# TopBoard.net
KiCad netlist of a schematic drawn in Altium Designer
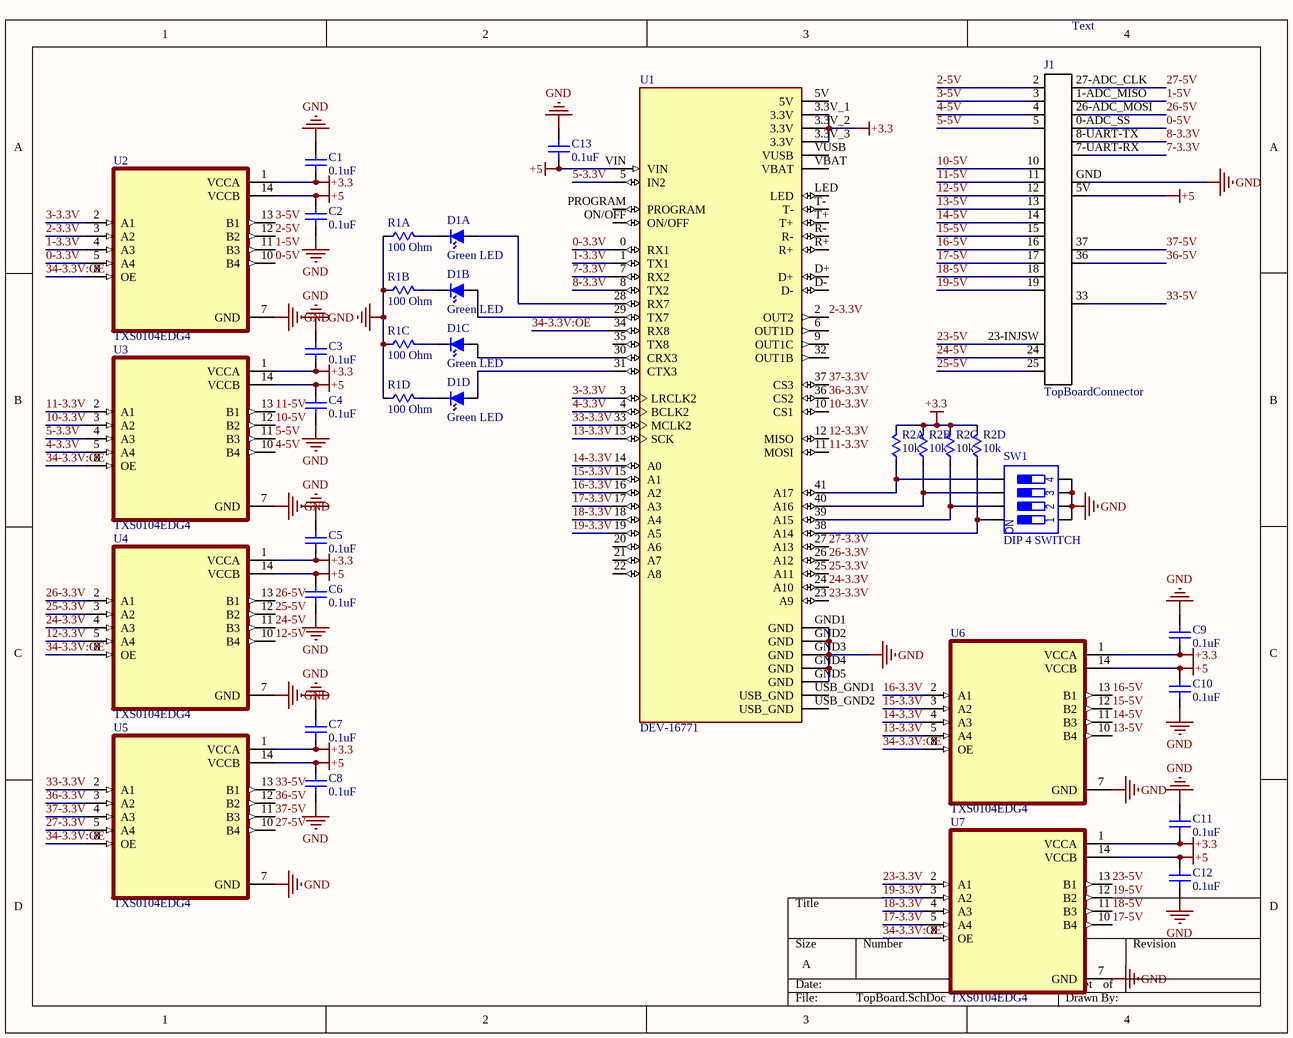
[diagram p0: TopBoard.SchDoc]

(export (version "E")
  (design (tool "Eeschema 10.0.6"))
  (components
    (comp (ref "C1")
      (value "0.1uF")
      (footprint "0805")
      (description "Cap 0805")
      (libsource (lib "Caps") (part "Cap_0805"))
    )
    (comp (ref "C2")
      (value "0.1uF")
      (footprint "0805")
      (description "Cap 0805")
      (libsource (lib "Caps") (part "Cap_0805"))
    )
    (comp (ref "C3")
      (value "0.1uF")
      (footprint "0805")
      (description "Cap 0805")
      (libsource (lib "Caps") (part "Cap_0805"))
    )
    (comp (ref "C4")
      (value "0.1uF")
      (footprint "0805")
      (description "Cap 0805")
      (libsource (lib "Caps") (part "Cap_0805"))
    )
    (comp (ref "C5")
      (value "0.1uF")
      (footprint "0805")
      (description "Cap 0805")
      (libsource (lib "Caps") (part "Cap_0805"))
    )
    (comp (ref "C6")
      (value "0.1uF")
      (footprint "0805")
      (description "Cap 0805")
      (libsource (lib "Caps") (part "Cap_0805"))
    )
    (comp (ref "C7")
      (value "0.1uF")
      (footprint "0805")
      (description "Cap 0805")
      (libsource (lib "Caps") (part "Cap_0805"))
    )
    (comp (ref "C8")
      (value "0.1uF")
      (footprint "0805")
      (description "Cap 0805")
      (libsource (lib "Caps") (part "Cap_0805"))
    )
    (comp (ref "C9")
      (value "0.1uF")
      (footprint "0805")
      (description "Cap 0805")
      (libsource (lib "Caps") (part "Cap_0805"))
    )
    (comp (ref "C10")
      (value "0.1uF")
      (footprint "0805")
      (description "Cap 0805")
      (libsource (lib "Caps") (part "Cap_0805"))
    )
    (comp (ref "C11")
      (value "0.1uF")
      (footprint "0805")
      (description "Cap 0805")
      (libsource (lib "Caps") (part "Cap_0805"))
    )
    (comp (ref "C12")
      (value "0.1uF")
      (footprint "0805")
      (description "Cap 0805")
      (libsource (lib "Caps") (part "Cap_0805"))
    )
    (comp (ref "C13")
      (value "0.1uF")
      (footprint "0805")
      (description "Cap 0805")
      (libsource (lib "Caps") (part "Cap_0805"))
    )
    (comp (ref "D1A")
      (value "Green LED")
      (footprint "Diode_0805")
      (description "Green 570nm LED Indication - Discrete 2.2V 0805 (2012 Metric)")
      (libsource (lib "LED") (part "LG R971-KN-1"))
    )
    (comp (ref "D1B")
      (value "Green LED")
      (footprint "Diode_0805")
      (description "Green 570nm LED Indication - Discrete 2.2V 0805 (2012 Metric)")
      (libsource (lib "LED") (part "LG R971-KN-1"))
    )
    (comp (ref "D1C")
      (value "Green LED")
      (footprint "Diode_0805")
      (description "Green 570nm LED Indication - Discrete 2.2V 0805 (2012 Metric)")
      (libsource (lib "LED") (part "LG R971-KN-1"))
    )
    (comp (ref "D1D")
      (value "Green LED")
      (footprint "Diode_0805")
      (description "Green 570nm LED Indication - Discrete 2.2V 0805 (2012 Metric)")
      (libsource (lib "LED") (part "LG R971-KN-1"))
    )
    (comp (ref "J1")
      (value "TopBoardConnector")
      (footprint "TopBoardConnector")
      (description "Connection to the bottom board")
      (libsource (lib "TopBoardConnector") (part "TopBoardConnector"))
    )
    (comp (ref "R1A")
      (value "100 Ohm")
      (footprint "0805")
      (description "Res 0805")
      (libsource (lib "Resistors") (part "Res_0805"))
    )
    (comp (ref "R1B")
      (value "100 Ohm")
      (footprint "0805")
      (description "Res 0805")
      (libsource (lib "Resistors") (part "Res_0805"))
    )
    (comp (ref "R1C")
      (value "100 Ohm")
      (footprint "0805")
      (description "Res 0805")
      (libsource (lib "Resistors") (part "Res_0805"))
    )
    (comp (ref "R1D")
      (value "100 Ohm")
      (footprint "0805")
      (description "Res 0805")
      (libsource (lib "Resistors") (part "Res_0805"))
    )
    (comp (ref "R2A")
      (value "10k")
      (footprint "0805")
      (description "Res 0805")
      (libsource (lib "Resistors") (part "Res_0805"))
    )
    (comp (ref "R2B")
      (value "10k")
      (footprint "0805")
      (description "Res 0805")
      (libsource (lib "Resistors") (part "Res_0805"))
    )
    (comp (ref "R2C")
      (value "10k")
      (footprint "0805")
      (description "Res 0805")
      (libsource (lib "Resistors") (part "Res_0805"))
    )
    (comp (ref "R2D")
      (value "10k")
      (footprint "0805")
      (description "Res 0805")
      (libsource (lib "Resistors") (part "Res_0805"))
    )
    (comp (ref "SW1")
      (value "DIP 4 SWITCH")
      (footprint "DS04-254-2-04BK-SMT-TR")
      (fields
        (field (name "MANUFACTURER") "CUI")
        (field (name "MANUFACTURER PART NUMBER") "DS04-254-2-04BK-SMT-TR")
      )
      (libsource (lib "DS04-254-2-04BK-SMT-TR") (part "DS04-254-2-04BK-SMT-TR"))
    )
    (comp (ref "U1")
      (value "DEV-16771")
      (footprint "MODULE_DEV-16771")
      (description "RT1062 Teensy 4.1 i.MX ARM Cortex-M7 MPU Embedded Evaluation Board")
      (libsource (lib "DEV-16771") (part "DEV-16771"))
    )
    (comp (ref "U2")
      (value "TXS0104EDG4")
      (footprint "SOIC127P600X175-14N")
      (fields (field (name "MF") "Texas Instruments"))
      (libsource (lib "TXS0104EDG4") (part "TXS0104EDG4"))
    )
    (comp (ref "U3")
      (value "TXS0104EDG4")
      (footprint "SOIC127P600X175-14N")
      (fields (field (name "MF") "Texas Instruments"))
      (libsource (lib "TXS0104EDG4") (part "TXS0104EDG4"))
    )
    (comp (ref "U4")
      (value "TXS0104EDG4")
      (footprint "SOIC127P600X175-14N")
      (fields (field (name "MF") "Texas Instruments"))
      (libsource (lib "TXS0104EDG4") (part "TXS0104EDG4"))
    )
    (comp (ref "U5")
      (value "TXS0104EDG4")
      (footprint "SOIC127P600X175-14N")
      (fields (field (name "MF") "Texas Instruments"))
      (libsource (lib "TXS0104EDG4") (part "TXS0104EDG4"))
    )
    (comp (ref "U6")
      (value "TXS0104EDG4")
      (footprint "SOIC127P600X175-14N")
      (fields (field (name "MF") "Texas Instruments"))
      (libsource (lib "TXS0104EDG4") (part "TXS0104EDG4"))
    )
    (comp (ref "U7")
      (value "TXS0104EDG4")
      (footprint "SOIC127P600X175-14N")
      (fields (field (name "MF") "Texas Instruments"))
      (libsource (lib "TXS0104EDG4") (part "TXS0104EDG4"))
    )
  )
  (nets
    (net (code "1") (name "+3.3") (class "Default")
      (node (ref "C1") (pin "1") (pinfunction "1_1") (pintype "passive"))
      (node (ref "C11") (pin "1") (pinfunction "1_1") (pintype "passive"))
      (node (ref "C3") (pin "1") (pinfunction "1_1") (pintype "passive"))
      (node (ref "C5") (pin "1") (pinfunction "1_1") (pintype "passive"))
      (node (ref "C7") (pin "1") (pinfunction "1_1") (pintype "passive"))
      (node (ref "C9") (pin "1") (pinfunction "1_1") (pintype "passive"))
      (node (ref "R2A") (pin "2") (pinfunction "2_2") (pintype "passive"))
      (node (ref "R2B") (pin "2") (pinfunction "2_2") (pintype "passive"))
      (node (ref "R2C") (pin "2") (pinfunction "2_2") (pintype "passive"))
      (node (ref "R2D") (pin "2") (pinfunction "2_2") (pintype "passive"))
      (node (ref "U1") (pin "3.3V_1") (pinfunction "3.3V_3.3V_1") (pintype "power_in"))
      (node (ref "U1") (pin "3.3V_2") (pinfunction "3.3V_3.3V_2") (pintype "power_in"))
      (node (ref "U1") (pin "3.3V_3") (pinfunction "3.3V_3.3V_3") (pintype "power_in"))
      (node (ref "U2") (pin "1") (pinfunction "VCCA_1") (pintype "power_in"))
      (node (ref "U3") (pin "1") (pinfunction "VCCA_1") (pintype "power_in"))
      (node (ref "U4") (pin "1") (pinfunction "VCCA_1") (pintype "power_in"))
      (node (ref "U5") (pin "1") (pinfunction "VCCA_1") (pintype "power_in"))
      (node (ref "U6") (pin "1") (pinfunction "VCCA_1") (pintype "power_in"))
      (node (ref "U7") (pin "1") (pinfunction "VCCA_1") (pintype "power_in"))
    )
    (net (code "2") (name "+5") (class "Default")
      (node (ref "C10") (pin "2") (pinfunction "2_2") (pintype "passive"))
      (node (ref "C12") (pin "2") (pinfunction "2_2") (pintype "passive"))
      (node (ref "C13") (pin "1") (pinfunction "1_1") (pintype "passive"))
      (node (ref "C2") (pin "2") (pinfunction "2_2") (pintype "passive"))
      (node (ref "C4") (pin "2") (pinfunction "2_2") (pintype "passive"))
      (node (ref "C6") (pin "2") (pinfunction "2_2") (pintype "passive"))
      (node (ref "C8") (pin "2") (pinfunction "2_2") (pintype "passive"))
      (node (ref "J1") (pin "5V") (pinfunction "5V_5V") (pintype "passive"))
      (node (ref "U1") (pin "VIN") (pinfunction "VIN_VIN") (pintype "input"))
      (node (ref "U2") (pin "14") (pinfunction "VCCB_14") (pintype "power_in"))
      (node (ref "U3") (pin "14") (pinfunction "VCCB_14") (pintype "power_in"))
      (node (ref "U4") (pin "14") (pinfunction "VCCB_14") (pintype "power_in"))
      (node (ref "U5") (pin "14") (pinfunction "VCCB_14") (pintype "power_in"))
      (node (ref "U6") (pin "14") (pinfunction "VCCB_14") (pintype "power_in"))
      (node (ref "U7") (pin "14") (pinfunction "VCCB_14") (pintype "power_in"))
    )
    (net (code "3") (name "/0-3.3V") (class "Default")
      (node (ref "U1") (pin "0") (pinfunction "RX1_0") (pintype "bidirectional"))
      (node (ref "U2") (pin "5") (pinfunction "A4_5") (pintype "input"))
    )
    (net (code "4") (name "/0-5V") (class "Default")
      (node (ref "J1") (pin "0-ADC_SS") (pinfunction "0-ADC_SS_0-ADC_SS") (pintype "passive"))
      (node (ref "U2") (pin "10") (pinfunction "B4_10") (pintype "output"))
    )
    (net (code "5") (name "/1-3.3V") (class "Default")
      (node (ref "U1") (pin "1") (pinfunction "TX1_1") (pintype "bidirectional"))
      (node (ref "U2") (pin "4") (pinfunction "A3_4") (pintype "input"))
    )
    (net (code "6") (name "/1-5V") (class "Default")
      (node (ref "J1") (pin "1-ADC_MISO") (pinfunction "1-ADC_MISO_1-ADC_MISO") (pintype "passive"))
      (node (ref "U2") (pin "11") (pinfunction "B3_11") (pintype "output"))
    )
    (net (code "7") (name "/2-3.3V") (class "Default")
      (node (ref "U1") (pin "2") (pinfunction "OUT2_2") (pintype "output"))
      (node (ref "U2") (pin "3") (pinfunction "A2_3") (pintype "input"))
    )
    (net (code "8") (name "/2-5V") (class "Default")
      (node (ref "J1") (pin "2") (pinfunction "2_2") (pintype "passive"))
      (node (ref "U2") (pin "12") (pinfunction "B2_12") (pintype "output"))
    )
    (net (code "9") (name "/3-3.3V") (class "Default")
      (node (ref "U1") (pin "3") (pinfunction "LRCLK2_3") (pintype "bidirectional"))
      (node (ref "U2") (pin "2") (pinfunction "A1_2") (pintype "input"))
    )
    (net (code "10") (name "/3-5V") (class "Default")
      (node (ref "J1") (pin "3") (pinfunction "3_3") (pintype "passive"))
      (node (ref "U2") (pin "13") (pinfunction "B1_13") (pintype "output"))
    )
    (net (code "11") (name "/4-3.3V") (class "Default")
      (node (ref "U1") (pin "4") (pinfunction "BCLK2_4") (pintype "bidirectional"))
      (node (ref "U3") (pin "5") (pinfunction "A4_5") (pintype "input"))
    )
    (net (code "12") (name "/4-5V") (class "Default")
      (node (ref "J1") (pin "4") (pinfunction "4_4") (pintype "passive"))
      (node (ref "U3") (pin "10") (pinfunction "B4_10") (pintype "output"))
    )
    (net (code "13") (name "/5-3.3V") (class "Default")
      (node (ref "U1") (pin "5") (pinfunction "IN2_5") (pintype "bidirectional"))
      (node (ref "U3") (pin "4") (pinfunction "A3_4") (pintype "input"))
    )
    (net (code "14") (name "/5-5V") (class "Default")
      (node (ref "J1") (pin "5") (pinfunction "5_5") (pintype "passive"))
      (node (ref "U3") (pin "11") (pinfunction "B3_11") (pintype "output"))
    )
    (net (code "15") (name "/7-3.3V") (class "Default")
      (node (ref "J1") (pin "7-UART-RX") (pinfunction "8-UART-RX_7-UART-RX") (pintype "passive"))
      (node (ref "U1") (pin "7") (pinfunction "RX2_7") (pintype "bidirectional"))
    )
    (net (code "16") (name "/8-3.3V") (class "Default")
      (node (ref "J1") (pin "8-UART-TX") (pinfunction "8-UART-TX_8-UART-TX") (pintype "passive"))
      (node (ref "U1") (pin "8") (pinfunction "TX2_8") (pintype "bidirectional"))
    )
    (net (code "17") (name "/10-3.3V") (class "Default")
      (node (ref "U1") (pin "10") (pinfunction "CS1_10") (pintype "bidirectional"))
      (node (ref "U3") (pin "3") (pinfunction "A2_3") (pintype "input"))
    )
    (net (code "18") (name "/10-5V") (class "Default")
      (node (ref "J1") (pin "10") (pinfunction "10_10") (pintype "passive"))
      (node (ref "U3") (pin "12") (pinfunction "B2_12") (pintype "output"))
    )
    (net (code "19") (name "/11-3.3V") (class "Default")
      (node (ref "U1") (pin "11") (pinfunction "MOSI_11") (pintype "bidirectional"))
      (node (ref "U3") (pin "2") (pinfunction "A1_2") (pintype "input"))
    )
    (net (code "20") (name "/11-5V") (class "Default")
      (node (ref "J1") (pin "11") (pinfunction "11_11") (pintype "passive"))
      (node (ref "U3") (pin "13") (pinfunction "B1_13") (pintype "output"))
    )
    (net (code "21") (name "/12-3.3V") (class "Default")
      (node (ref "U1") (pin "12") (pinfunction "MISO_12") (pintype "bidirectional"))
      (node (ref "U4") (pin "5") (pinfunction "A4_5") (pintype "input"))
    )
    (net (code "22") (name "/12-5V") (class "Default")
      (node (ref "J1") (pin "12") (pinfunction "12_12") (pintype "passive"))
      (node (ref "U4") (pin "10") (pinfunction "B4_10") (pintype "output"))
    )
    (net (code "23") (name "/13-3.3V") (class "Default")
      (node (ref "U1") (pin "13") (pinfunction "SCK_13") (pintype "bidirectional"))
      (node (ref "U6") (pin "5") (pinfunction "A4_5") (pintype "input"))
    )
    (net (code "24") (name "/13-5V") (class "Default")
      (node (ref "J1") (pin "13") (pinfunction "13_13") (pintype "passive"))
      (node (ref "U6") (pin "10") (pinfunction "B4_10") (pintype "output"))
    )
    (net (code "25") (name "/14-3.3V") (class "Default")
      (node (ref "U1") (pin "14") (pinfunction "A0_14") (pintype "bidirectional"))
      (node (ref "U6") (pin "4") (pinfunction "A3_4") (pintype "input"))
    )
    (net (code "26") (name "/14-5V") (class "Default")
      (node (ref "J1") (pin "14") (pinfunction "14_14") (pintype "passive"))
      (node (ref "U6") (pin "11") (pinfunction "B3_11") (pintype "output"))
    )
    (net (code "27") (name "/15-3.3V") (class "Default")
      (node (ref "U1") (pin "15") (pinfunction "A1_15") (pintype "bidirectional"))
      (node (ref "U6") (pin "3") (pinfunction "A2_3") (pintype "input"))
    )
    (net (code "28") (name "/15-5V") (class "Default")
      (node (ref "J1") (pin "15") (pinfunction "15_15") (pintype "passive"))
      (node (ref "U6") (pin "12") (pinfunction "B2_12") (pintype "output"))
    )
    (net (code "29") (name "/16-3.3V") (class "Default")
      (node (ref "U1") (pin "16") (pinfunction "A2_16") (pintype "bidirectional"))
      (node (ref "U6") (pin "2") (pinfunction "A1_2") (pintype "input"))
    )
    (net (code "30") (name "/16-5V") (class "Default")
      (node (ref "J1") (pin "16") (pinfunction "16_16") (pintype "passive"))
      (node (ref "U6") (pin "13") (pinfunction "B1_13") (pintype "output"))
    )
    (net (code "31") (name "/17-3.3V") (class "Default")
      (node (ref "U1") (pin "17") (pinfunction "A3_17") (pintype "bidirectional"))
      (node (ref "U7") (pin "5") (pinfunction "A4_5") (pintype "input"))
    )
    (net (code "32") (name "/17-5V") (class "Default")
      (node (ref "J1") (pin "17") (pinfunction "17_17") (pintype "passive"))
      (node (ref "U7") (pin "10") (pinfunction "B4_10") (pintype "output"))
    )
    (net (code "33") (name "/18-3.3V") (class "Default")
      (node (ref "U1") (pin "18") (pinfunction "A4_18") (pintype "bidirectional"))
      (node (ref "U7") (pin "4") (pinfunction "A3_4") (pintype "input"))
    )
    (net (code "34") (name "/18-5V") (class "Default")
      (node (ref "J1") (pin "18") (pinfunction "18_18") (pintype "passive"))
      (node (ref "U7") (pin "11") (pinfunction "B3_11") (pintype "output"))
    )
    (net (code "35") (name "/19-3.3V") (class "Default")
      (node (ref "U1") (pin "19") (pinfunction "A5_19") (pintype "bidirectional"))
      (node (ref "U7") (pin "3") (pinfunction "A2_3") (pintype "input"))
    )
    (net (code "36") (name "/19-5V") (class "Default")
      (node (ref "J1") (pin "19") (pinfunction "19_19") (pintype "passive"))
      (node (ref "U7") (pin "12") (pinfunction "B2_12") (pintype "output"))
    )
    (net (code "37") (name "/23-3.3V") (class "Default")
      (node (ref "U1") (pin "23") (pinfunction "A9_23") (pintype "bidirectional"))
      (node (ref "U7") (pin "2") (pinfunction "A1_2") (pintype "input"))
    )
    (net (code "38") (name "/23-5V") (class "Default")
      (node (ref "J1") (pin "23-INJSW") (pinfunction "23-INJSW_23-INJSW") (pintype "passive"))
      (node (ref "U7") (pin "13") (pinfunction "B1_13") (pintype "output"))
    )
    (net (code "39") (name "/24-3.3V") (class "Default")
      (node (ref "U1") (pin "24") (pinfunction "A10_24") (pintype "bidirectional"))
      (node (ref "U4") (pin "4") (pinfunction "A3_4") (pintype "input"))
    )
    (net (code "40") (name "/24-5V") (class "Default")
      (node (ref "J1") (pin "24") (pinfunction "24_24") (pintype "passive"))
      (node (ref "U4") (pin "11") (pinfunction "B3_11") (pintype "output"))
    )
    (net (code "41") (name "/25-3.3V") (class "Default")
      (node (ref "U1") (pin "25") (pinfunction "A11_25") (pintype "bidirectional"))
      (node (ref "U4") (pin "3") (pinfunction "A2_3") (pintype "input"))
    )
    (net (code "42") (name "/25-5V") (class "Default")
      (node (ref "J1") (pin "25") (pinfunction "25_25") (pintype "passive"))
      (node (ref "U4") (pin "12") (pinfunction "B2_12") (pintype "output"))
    )
    (net (code "43") (name "/26-3.3V") (class "Default")
      (node (ref "U1") (pin "26") (pinfunction "A12_26") (pintype "bidirectional"))
      (node (ref "U4") (pin "2") (pinfunction "A1_2") (pintype "input"))
    )
    (net (code "44") (name "/26-5V") (class "Default")
      (node (ref "J1") (pin "26-ADC_MOSI") (pinfunction "26-ADC_MOSI_26-ADC_MOSI") (pintype "passive"))
      (node (ref "U4") (pin "13") (pinfunction "B1_13") (pintype "output"))
    )
    (net (code "45") (name "/27-3.3V") (class "Default")
      (node (ref "U1") (pin "27") (pinfunction "A13_27") (pintype "bidirectional"))
      (node (ref "U5") (pin "5") (pinfunction "A4_5") (pintype "input"))
    )
    (net (code "46") (name "/27-5V") (class "Default")
      (node (ref "J1") (pin "27-ADC_CLK") (pinfunction "27-ADC_CLK_27-ADC_CLK") (pintype "passive"))
      (node (ref "U5") (pin "10") (pinfunction "B4_10") (pintype "output"))
    )
    (net (code "47") (name "/33-3.3V") (class "Default")
      (node (ref "U1") (pin "33") (pinfunction "MCLK2_33") (pintype "bidirectional"))
      (node (ref "U5") (pin "2") (pinfunction "A1_2") (pintype "input"))
    )
    (net (code "48") (name "/33-5V") (class "Default")
      (node (ref "J1") (pin "33") (pinfunction "33_33") (pintype "passive"))
      (node (ref "U5") (pin "13") (pinfunction "B1_13") (pintype "output"))
    )
    (net (code "49") (name "/34-3.3V:OE") (class "Default")
      (node (ref "U1") (pin "34") (pinfunction "RX8_34") (pintype "bidirectional"))
      (node (ref "U2") (pin "8") (pinfunction "OE_8") (pintype "input"))
      (node (ref "U3") (pin "8") (pinfunction "OE_8") (pintype "input"))
      (node (ref "U4") (pin "8") (pinfunction "OE_8") (pintype "input"))
      (node (ref "U5") (pin "8") (pinfunction "OE_8") (pintype "input"))
      (node (ref "U6") (pin "8") (pinfunction "OE_8") (pintype "input"))
      (node (ref "U7") (pin "8") (pinfunction "OE_8") (pintype "input"))
    )
    (net (code "50") (name "/36-3.3V") (class "Default")
      (node (ref "U1") (pin "36") (pinfunction "CS2_36") (pintype "bidirectional"))
      (node (ref "U5") (pin "3") (pinfunction "A2_3") (pintype "input"))
    )
    (net (code "51") (name "/36-5V") (class "Default")
      (node (ref "J1") (pin "36") (pinfunction "36_36") (pintype "passive"))
      (node (ref "U5") (pin "12") (pinfunction "B2_12") (pintype "output"))
    )
    (net (code "52") (name "/37-3.3V") (class "Default")
      (node (ref "U1") (pin "37") (pinfunction "CS3_37") (pintype "bidirectional"))
      (node (ref "U5") (pin "4") (pinfunction "A3_4") (pintype "input"))
    )
    (net (code "53") (name "/37-5V") (class "Default")
      (node (ref "J1") (pin "37") (pinfunction "37_37") (pintype "passive"))
      (node (ref "U5") (pin "11") (pinfunction "B3_11") (pintype "output"))
    )
    (net (code "54") (name "GND") (class "Default")
      (node (ref "C1") (pin "2") (pinfunction "2_2") (pintype "passive"))
      (node (ref "C10") (pin "1") (pinfunction "1_1") (pintype "passive"))
      (node (ref "C11") (pin "2") (pinfunction "2_2") (pintype "passive"))
      (node (ref "C12") (pin "1") (pinfunction "1_1") (pintype "passive"))
      (node (ref "C13") (pin "2") (pinfunction "2_2") (pintype "passive"))
      (node (ref "C2") (pin "1") (pinfunction "1_1") (pintype "passive"))
      (node (ref "C3") (pin "2") (pinfunction "2_2") (pintype "passive"))
      (node (ref "C4") (pin "1") (pinfunction "1_1") (pintype "passive"))
      (node (ref "C5") (pin "2") (pinfunction "2_2") (pintype "passive"))
      (node (ref "C6") (pin "1") (pinfunction "1_1") (pintype "passive"))
      (node (ref "C7") (pin "2") (pinfunction "2_2") (pintype "passive"))
      (node (ref "C8") (pin "1") (pinfunction "1_1") (pintype "passive"))
      (node (ref "C9") (pin "2") (pinfunction "2_2") (pintype "passive"))
      (node (ref "J1") (pin "GND") (pinfunction "GND_GND") (pintype "passive"))
      (node (ref "R1A") (pin "1") (pinfunction "1_1") (pintype "passive"))
      (node (ref "R1B") (pin "1") (pinfunction "1_1") (pintype "passive"))
      (node (ref "R1C") (pin "1") (pinfunction "1_1") (pintype "passive"))
      (node (ref "R1D") (pin "1") (pinfunction "1_1") (pintype "passive"))
      (node (ref "SW1") (pin "5") (pinfunction "5_5") (pintype "passive"))
      (node (ref "SW1") (pin "6") (pinfunction "6_6") (pintype "passive"))
      (node (ref "SW1") (pin "7") (pinfunction "7_7") (pintype "passive"))
      (node (ref "SW1") (pin "8") (pinfunction "8_8") (pintype "passive"))
      (node (ref "U1") (pin "GND1") (pinfunction "GND_GND1") (pintype "power_in"))
      (node (ref "U1") (pin "GND2") (pinfunction "GND_GND2") (pintype "power_in"))
      (node (ref "U1") (pin "GND3") (pinfunction "GND_GND3") (pintype "power_in"))
      (node (ref "U1") (pin "GND4") (pinfunction "GND_GND4") (pintype "power_in"))
      (node (ref "U1") (pin "GND5") (pinfunction "GND_GND5") (pintype "power_in"))
      (node (ref "U2") (pin "7") (pinfunction "GND_7") (pintype "power_in"))
      (node (ref "U3") (pin "7") (pinfunction "GND_7") (pintype "power_in"))
      (node (ref "U4") (pin "7") (pinfunction "GND_7") (pintype "power_in"))
      (node (ref "U5") (pin "7") (pinfunction "GND_7") (pintype "power_in"))
      (node (ref "U6") (pin "7") (pinfunction "GND_7") (pintype "power_in"))
      (node (ref "U7") (pin "7") (pinfunction "GND_7") (pintype "power_in"))
    )
    (net (code "55") (name "Net-(D1A-Pad-)") (class "Default")
      (node (ref "D1A") (pin "-") (pinfunction "-_-") (pintype "passive"))
      (node (ref "R1A") (pin "2") (pinfunction "2_2") (pintype "passive"))
    )
    (net (code "56") (name "Net-(D1B-Pad-)") (class "Default")
      (node (ref "D1B") (pin "-") (pinfunction "-_-") (pintype "passive"))
      (node (ref "R1B") (pin "2") (pinfunction "2_2") (pintype "passive"))
    )
    (net (code "57") (name "Net-(D1C-Pad-)") (class "Default")
      (node (ref "D1C") (pin "-") (pinfunction "-_-") (pintype "passive"))
      (node (ref "R1C") (pin "2") (pinfunction "2_2") (pintype "passive"))
    )
    (net (code "58") (name "Net-(D1D-Pad-)") (class "Default")
      (node (ref "D1D") (pin "-") (pinfunction "-_-") (pintype "passive"))
      (node (ref "R1D") (pin "2") (pinfunction "2_2") (pintype "passive"))
    )
    (net (code "59") (name "Net-(U1-A14)") (class "Default")
      (node (ref "R2D") (pin "1") (pinfunction "1_1") (pintype "passive"))
      (node (ref "SW1") (pin "1") (pinfunction "1_1") (pintype "passive"))
      (node (ref "U1") (pin "38") (pinfunction "A14_38") (pintype "bidirectional"))
    )
    (net (code "60") (name "Net-(U1-A15)") (class "Default")
      (node (ref "R2C") (pin "1") (pinfunction "1_1") (pintype "passive"))
      (node (ref "SW1") (pin "2") (pinfunction "2_2") (pintype "passive"))
      (node (ref "U1") (pin "39") (pinfunction "A15_39") (pintype "bidirectional"))
    )
    (net (code "61") (name "Net-(U1-A16)") (class "Default")
      (node (ref "R2B") (pin "1") (pinfunction "1_1") (pintype "passive"))
      (node (ref "SW1") (pin "3") (pinfunction "3_3") (pintype "passive"))
      (node (ref "U1") (pin "40") (pinfunction "A16_40") (pintype "bidirectional"))
    )
    (net (code "62") (name "Net-(U1-A17)") (class "Default")
      (node (ref "R2A") (pin "1") (pinfunction "1_1") (pintype "passive"))
      (node (ref "SW1") (pin "4") (pinfunction "4_4") (pintype "passive"))
      (node (ref "U1") (pin "41") (pinfunction "A17_41") (pintype "bidirectional"))
    )
    (net (code "63") (name "Net-(U1-CRX3)") (class "Default")
      (node (ref "D1C") (pin "+") (pinfunction "+_+") (pintype "passive"))
      (node (ref "U1") (pin "30") (pinfunction "CRX3_30") (pintype "bidirectional"))
    )
    (net (code "64") (name "Net-(U1-CTX3)") (class "Default")
      (node (ref "D1D") (pin "+") (pinfunction "+_+") (pintype "passive"))
      (node (ref "U1") (pin "31") (pinfunction "CTX3_31") (pintype "bidirectional"))
    )
    (net (code "65") (name "Net-(U1-RX7)") (class "Default")
      (node (ref "D1A") (pin "+") (pinfunction "+_+") (pintype "passive"))
      (node (ref "U1") (pin "28") (pinfunction "RX7_28") (pintype "bidirectional"))
    )
    (net (code "66") (name "Net-(U1-TX7)") (class "Default")
      (node (ref "D1B") (pin "+") (pinfunction "+_+") (pintype "passive"))
      (node (ref "U1") (pin "29") (pinfunction "TX7_29") (pintype "bidirectional"))
    )
    (net (code "67") (name "unconnected-(U1-A6-Pad20)") (class "Default")
      (node (ref "U1") (pin "20") (pinfunction "A6_20") (pintype "bidirectional"))
    )
    (net (code "68") (name "unconnected-(U1-A7-Pad21)") (class "Default")
      (node (ref "U1") (pin "21") (pinfunction "A7_21") (pintype "bidirectional"))
    )
    (net (code "69") (name "unconnected-(U1-A8-Pad22)") (class "Default")
      (node (ref "U1") (pin "22") (pinfunction "A8_22") (pintype "bidirectional"))
    )
    (net (code "70") (name "unconnected-(U1-OUT1B-Pad32)") (class "Default")
      (node (ref "U1") (pin "32") (pinfunction "OUT1B_32") (pintype "output"))
    )
    (net (code "71") (name "unconnected-(U1-OUT1C-Pad9)") (class "Default")
      (node (ref "U1") (pin "9") (pinfunction "OUT1C_9") (pintype "output"))
    )
    (net (code "72") (name "unconnected-(U1-OUT1D-Pad6)") (class "Default")
      (node (ref "U1") (pin "6") (pinfunction "OUT1D_6") (pintype "output"))
    )
    (net (code "73") (name "unconnected-(U1-Pad5V)") (class "Default")
      (node (ref "U1") (pin "5V") (pinfunction "5V_5V") (pintype "power_in"))
    )
    (net (code "74") (name "unconnected-(U1-PadD+)") (class "Default")
      (node (ref "U1") (pin "D+") (pinfunction "D+_D+") (pintype "bidirectional"))
    )
    (net (code "75") (name "unconnected-(U1-PadD-)") (class "Default")
      (node (ref "U1") (pin "D-") (pinfunction "D-_D-") (pintype "bidirectional"))
    )
    (net (code "76") (name "unconnected-(U1-PadLED)") (class "Default")
      (node (ref "U1") (pin "LED") (pinfunction "LED_LED") (pintype "bidirectional"))
    )
    (net (code "77") (name "unconnected-(U1-PadON{slash}OFF)") (class "Default")
      (node (ref "U1") (pin "ON/OFF") (pinfunction "ON/OFF_ON/OFF") (pintype "bidirectional"))
    )
    (net (code "78") (name "unconnected-(U1-PadPROGRAM)") (class "Default")
      (node (ref "U1") (pin "PROGRAM") (pinfunction "PROGRAM_PROGRAM") (pintype "bidirectional"))
    )
    (net (code "79") (name "unconnected-(U1-PadR+)") (class "Default")
      (node (ref "U1") (pin "R+") (pinfunction "R+_R+") (pintype "bidirectional"))
    )
    (net (code "80") (name "unconnected-(U1-PadR-)") (class "Default")
      (node (ref "U1") (pin "R-") (pinfunction "R-_R-") (pintype "bidirectional"))
    )
    (net (code "81") (name "unconnected-(U1-PadT+)") (class "Default")
      (node (ref "U1") (pin "T+") (pinfunction "T+_T+") (pintype "bidirectional"))
    )
    (net (code "82") (name "unconnected-(U1-PadT-)") (class "Default")
      (node (ref "U1") (pin "T-") (pinfunction "T-_T-") (pintype "bidirectional"))
    )
    (net (code "83") (name "unconnected-(U1-PadVBAT)") (class "Default")
      (node (ref "U1") (pin "VBAT") (pinfunction "VBAT_VBAT") (pintype "passive"))
    )
    (net (code "84") (name "unconnected-(U1-PadVUSB)") (class "Default")
      (node (ref "U1") (pin "VUSB") (pinfunction "VUSB_VUSB") (pintype "passive"))
    )
    (net (code "85") (name "unconnected-(U1-TX8-Pad35)") (class "Default")
      (node (ref "U1") (pin "35") (pinfunction "TX8_35") (pintype "bidirectional"))
    )
    (net (code "86") (name "unconnected-(U1-USB_GND-PadUSB_GND1)") (class "Default")
      (node (ref "U1") (pin "USB_GND1") (pinfunction "USB_GND_USB_GND1") (pintype "power_in"))
    )
    (net (code "87") (name "unconnected-(U1-USB_GND-PadUSB_GND2)") (class "Default")
      (node (ref "U1") (pin "USB_GND2") (pinfunction "USB_GND_USB_GND2") (pintype "power_in"))
    )
  )
)
